# AnalogMux.net
KiCad netlist of a schematic drawn in Altium Designer
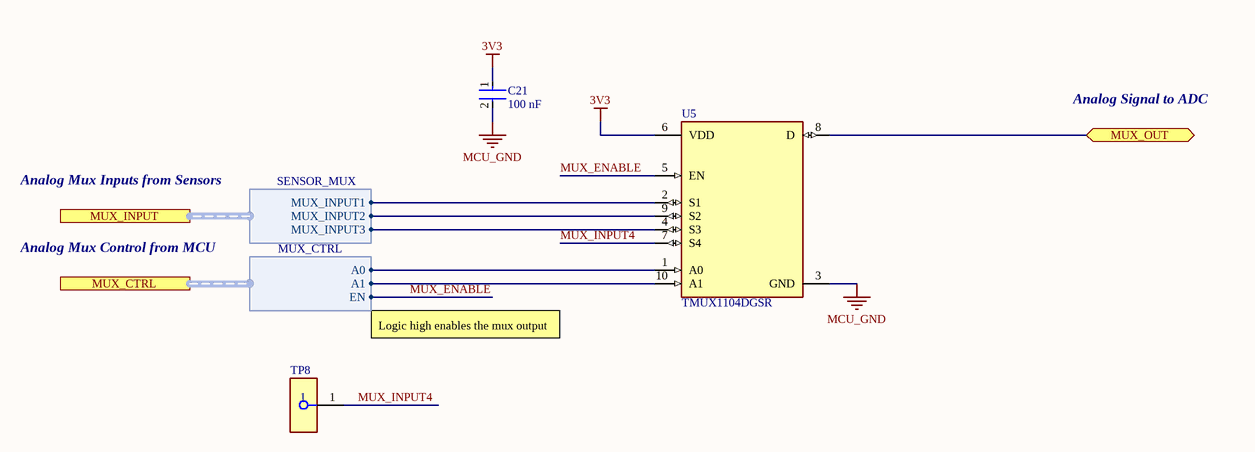
[diagram p0: AnalogMux.SchDoc]

(export (version "E")
  (design (tool "Eeschema 10.0.6"))
  (components
    (comp (ref "C21")
      (value "CC0603KRX7R7BB104")
      (footprint "FP-CC0603-DA-MFG")
      (description "CAP CER 0.1UF 16V X7R 0603")
      (fields
        (field (name "OCTOPART") "https://octopart.com/cc0603krx7r7bb104-yageo-192941")
        (field (name "TOLERANCE") "0.1")
        (field (name "CAPACITANCE") "100 nF")
      )
      (libsource (lib "Altium Content Vault") (part "11868f565c42a9108669ba33697ecf6"))
    )
    (comp (ref "TP8")
      (value "S2761-46R")
      (footprint "FP-S2761-46R-MFG")
      (description "PC TEST POINT NATURAL")
      (libsource (lib "Altium Content Vault") (part "98815daf2f2c152b0c43f5ab9800df6"))
    )
    (comp (ref "U5")
      (value "TMUX1104DGSR")
      (footprint "FP-DGS0010A-MFG")
      (description "IC SWITCH SINGLE 10VSSOP")
      (libsource (lib "Altium Content Vault") (part "177f213541e076a53b59290d3bf4553"))
    )
  )
  (nets
    (net (code "3") (name "/A0") (class "Default")
      (node (ref "U5") (pin "1") (pinfunction "A0_1") (pintype "input"))
    )
    (net (code "4") (name "/A1") (class "Default")
      (node (ref "U5") (pin "10") (pinfunction "A1_10") (pintype "input"))
    )
    (net (code "5") (name "/MUX_ENABLE") (class "Default")
      (node (ref "U5") (pin "5") (pinfunction "EN_5") (pintype "input"))
    )
    (net (code "6") (name "/MUX_INPUT1") (class "Default")
      (node (ref "U5") (pin "2") (pinfunction "S1_2") (pintype "bidirectional"))
    )
    (net (code "7") (name "/MUX_INPUT2") (class "Default")
      (node (ref "U5") (pin "9") (pinfunction "S2_9") (pintype "bidirectional"))
    )
    (net (code "8") (name "/MUX_INPUT3") (class "Default")
      (node (ref "U5") (pin "4") (pinfunction "S3_4") (pintype "bidirectional"))
    )
    (net (code "9") (name "/MUX_INPUT4") (class "Default")
      (node (ref "TP8") (pin "1") (pinfunction "1_1") (pintype "passive"))
      (node (ref "U5") (pin "7") (pinfunction "S4_7") (pintype "bidirectional"))
    )
    (net (code "10") (name "/MUX_OUT") (class "Default")
      (node (ref "U5") (pin "8") (pinfunction "D_8") (pintype "bidirectional"))
    )
    (net (code "13") (name "3V3") (class "Default")
      (node (ref "C21") (pin "1") (pinfunction "1_1") (pintype "passive"))
      (node (ref "U5") (pin "6") (pinfunction "VDD_6") (pintype "power_in"))
    )
    (net (code "14") (name "MCU_GND") (class "Default")
      (node (ref "C21") (pin "2") (pinfunction "2_2") (pintype "passive"))
      (node (ref "U5") (pin "3") (pinfunction "GND_3") (pintype "power_in"))
    )
  )
)
